# leaf-heater-element-rev1.net
KiCad netlist of a schematic drawn in EAGLE
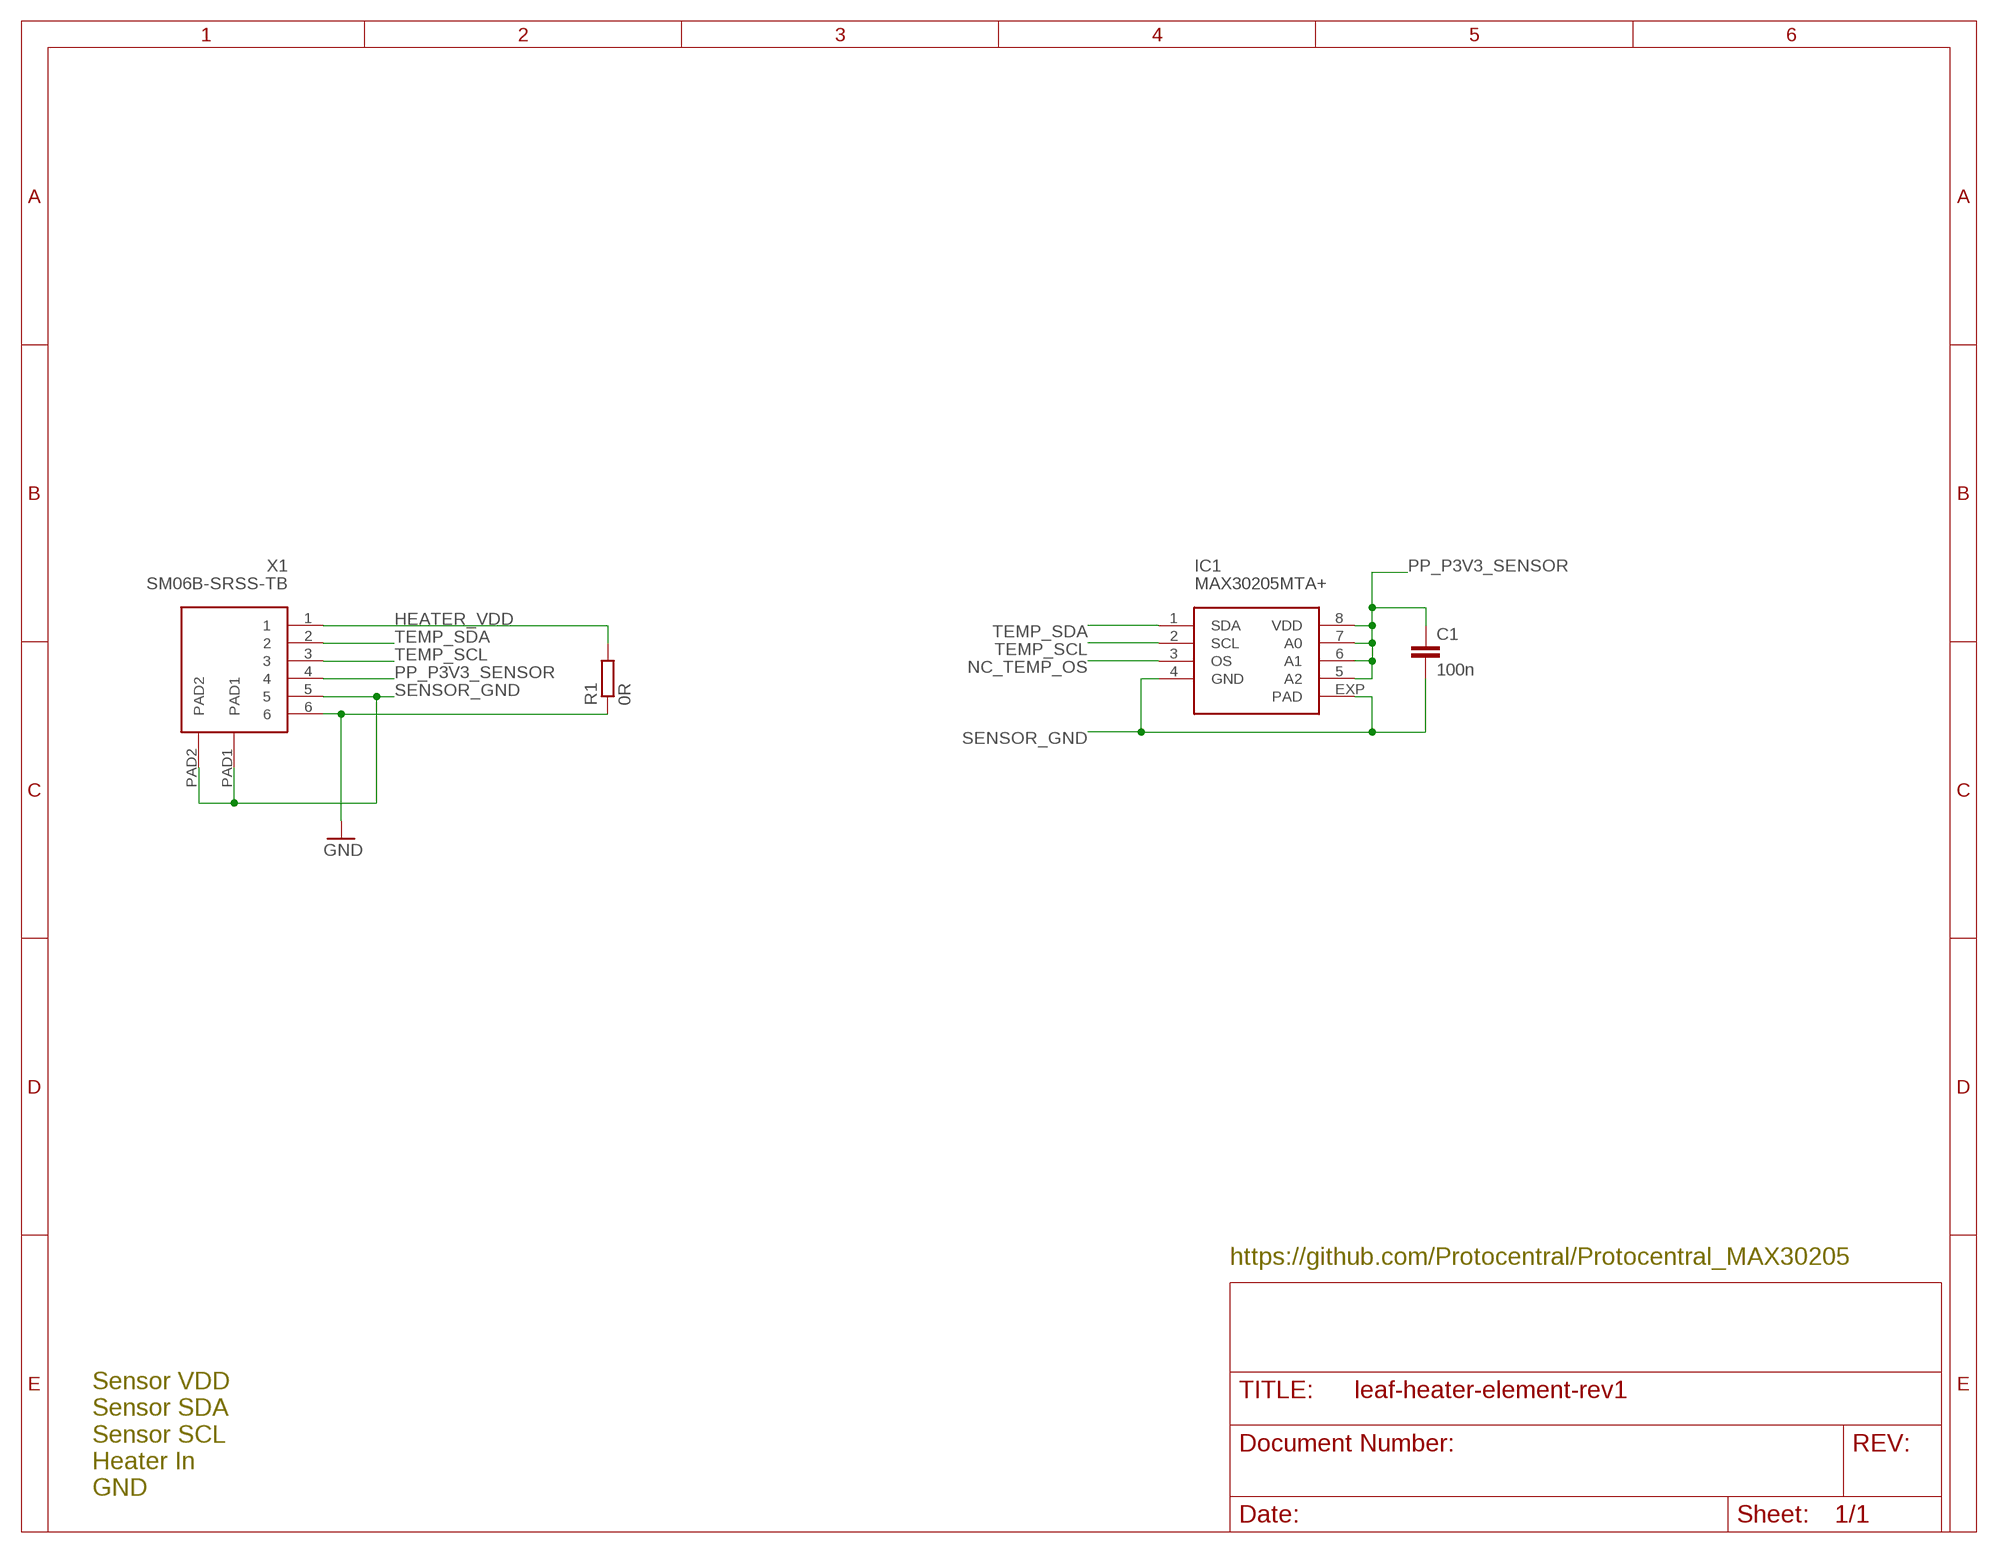
[diagram p0: schematic, sheet 1]

(export (version "E")
  (design (tool "Eeschema 10.0.6"))
  (components
    (comp (ref "C1")
      (value "100n")
      (footprint "eagle-import:C0402")
      (libsource (lib "eagle-import") (part "C-EUC0402"))
    )
    (comp (ref "IC1")
      (value "MAX30205MTA+")
      (footprint "eagle-import:TDFN-08")
      (libsource (lib "eagle-import") (part "MAX30205MTA+"))
    )
    (comp (ref "R1")
      (value "0R")
      (footprint "eagle-import:R0603")
      (libsource (lib "eagle-import") (part "R-EU_R0603"))
    )
    (comp (ref "X1")
      (value "SM06B-SRSS-TB")
      (footprint "eagle-import:JST-SM06B-SRSS-TB")
      (libsource (lib "eagle-import") (part "JST-SH-6PIN"))
    )
  )
  (nets
    (net (code "1") (name "/HEATER_VDD") (class "Default")
      (node (ref "R1") (pin "2") (pinfunction "2_2") (pintype "passive"))
      (node (ref "X1") (pin "1") (pinfunction "1_1") (pintype "bidirectional"))
    )
    (net (code "2") (name "/NC_TEMP_OS") (class "Default")
      (node (ref "IC1") (pin "3") (pinfunction "OS_3") (pintype "bidirectional"))
    )
    (net (code "3") (name "/PP_P3V3_SENSOR") (class "Default")
      (node (ref "C1") (pin "1") (pinfunction "1_1") (pintype "passive"))
      (node (ref "IC1") (pin "5") (pinfunction "A2_5") (pintype "bidirectional"))
      (node (ref "IC1") (pin "6") (pinfunction "A1_6") (pintype "bidirectional"))
      (node (ref "IC1") (pin "7") (pinfunction "A0_7") (pintype "bidirectional"))
      (node (ref "IC1") (pin "8") (pinfunction "VDD_8") (pintype "bidirectional"))
      (node (ref "X1") (pin "4") (pinfunction "4_4") (pintype "bidirectional"))
    )
    (net (code "4") (name "/SENSOR_GND") (class "Default")
      (node (ref "C1") (pin "2") (pinfunction "2_2") (pintype "passive"))
      (node (ref "IC1") (pin "4") (pinfunction "GND_4") (pintype "bidirectional"))
      (node (ref "IC1") (pin "EXP") (pinfunction "PAD_EXP") (pintype "bidirectional"))
      (node (ref "X1") (pin "5") (pinfunction "5_5") (pintype "bidirectional"))
      (node (ref "X1") (pin "PAD1") (pinfunction "PAD1_PAD1") (pintype "bidirectional"))
      (node (ref "X1") (pin "PAD2") (pinfunction "PAD2_PAD2") (pintype "bidirectional"))
    )
    (net (code "5") (name "/TEMP_SCL") (class "Default")
      (node (ref "IC1") (pin "2") (pinfunction "SCL_2") (pintype "bidirectional"))
      (node (ref "X1") (pin "3") (pinfunction "3_3") (pintype "bidirectional"))
    )
    (net (code "6") (name "/TEMP_SDA") (class "Default")
      (node (ref "IC1") (pin "1") (pinfunction "SDA_1") (pintype "bidirectional"))
      (node (ref "X1") (pin "2") (pinfunction "2_2") (pintype "bidirectional"))
    )
    (net (code "7") (name "GND") (class "Default")
      (node (ref "R1") (pin "1") (pinfunction "1_1") (pintype "passive"))
      (node (ref "X1") (pin "6") (pinfunction "6_6") (pintype "bidirectional"))
    )
  )
)
